# SCH_lab_1_2026-07-23.net
KiCad netlist of a schematic drawn in EasyEDA
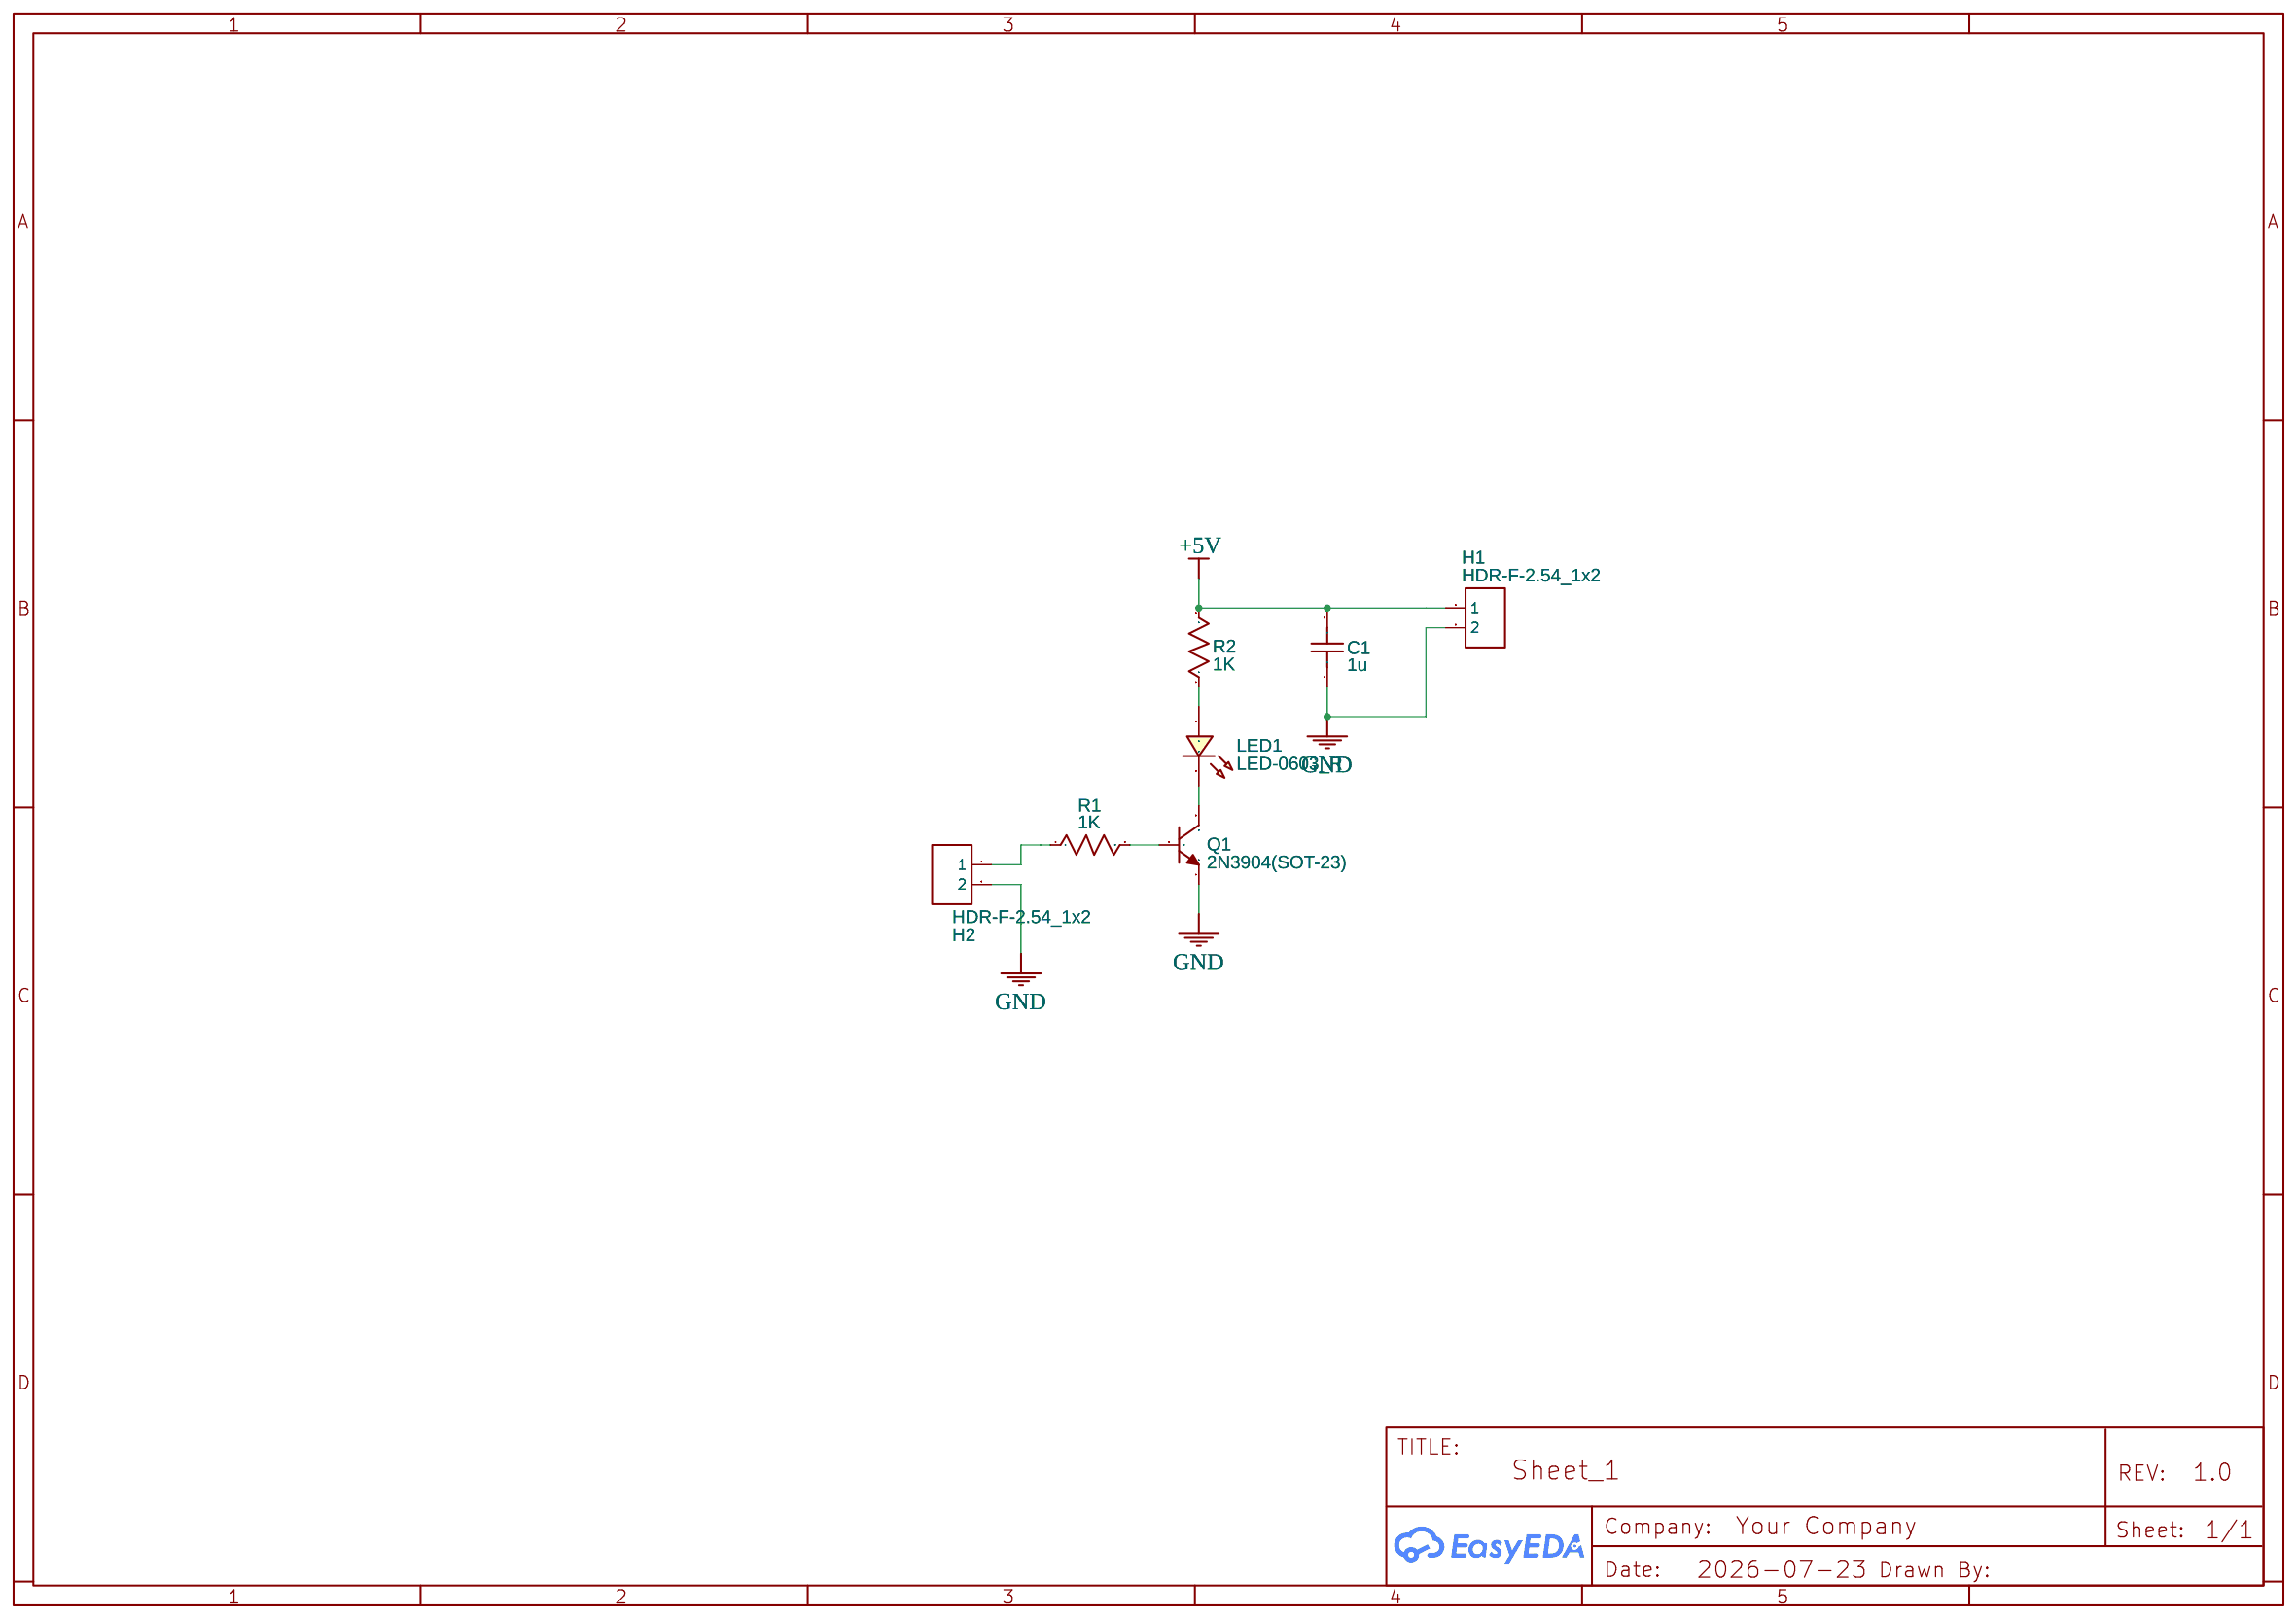
[diagram p0: schematic sheet]

(export (version "E")
  (design (tool "Eeschema 10.0.6"))
  (components
    (comp (ref "C1") (value "1u") (libsource (lib "") (part "Capacitor_US")))
    (comp (ref "H1") (value "HDR-F-2.54_1x2") (libsource (lib "") (part "HDR-F-2.54_1x2_1")))
    (comp (ref "H2") (value "HDR-F-2.54_1x2") (libsource (lib "") (part "HDR-F-2.54_1x2")))
    (comp (ref "LED1")
      (value "LED-0603_R")
      (fields
        (field (name "Manufacturer Part") "19-217/R6C-AL1M2VY/3T")
        (field (name "Manufacturer") "EVERLIGHT(台湾亿光)")
      )
      (libsource (lib "") (part "LED-0603_R"))
    )
    (comp (ref "Q1")
      (value "2N3904(SOT-23)")
      (fields (field (name "Manufacturer Part") "2n3904S-RTK/PS") (field (name "Manufacturer") "KEC"))
      (libsource (lib "") (part "2N3904(SOT-23)"))
    )
    (comp (ref "R1") (value "1K") (libsource (lib "") (part "Resistor_US_1")))
    (comp (ref "R2") (value "1K") (libsource (lib "") (part "Resistor_US")))
  )
  (nets
    (net (code "1") (name "+5V") (class "Default")
      (node (ref "C1") (pin "2") (pinfunction "2_2") (pintype "unspecified"))
      (node (ref "H1") (pin "1") (pinfunction "1_1") (pintype "input"))
      (node (ref "R2") (pin "2") (pinfunction "2_2") (pintype "unspecified"))
    )
    (net (code "2") (name "GND") (class "Default")
      (node (ref "C1") (pin "1") (pinfunction "1_1") (pintype "unspecified"))
      (node (ref "H1") (pin "2") (pinfunction "2_2") (pintype "input"))
      (node (ref "H2") (pin "2") (pinfunction "2_2") (pintype "input"))
      (node (ref "Q1") (pin "1") (pinfunction "E_1") (pintype "input"))
    )
    (net (code "3") (name "Net-(H2-Pad1)") (class "Default")
      (node (ref "H2") (pin "1") (pinfunction "1_1") (pintype "input"))
      (node (ref "R1") (pin "1") (pinfunction "1_1") (pintype "unspecified"))
    )
    (net (code "4") (name "Net-(LED1-Pad1)") (class "Default")
      (node (ref "LED1") (pin "1") (pinfunction "1_1") (pintype "unspecified"))
      (node (ref "R2") (pin "1") (pinfunction "1_1") (pintype "unspecified"))
    )
    (net (code "5") (name "Net-(Q1-B)") (class "Default")
      (node (ref "Q1") (pin "2") (pinfunction "B_2") (pintype "input"))
      (node (ref "R1") (pin "2") (pinfunction "2_2") (pintype "unspecified"))
    )
    (net (code "6") (name "Net-(Q1-C)") (class "Default")
      (node (ref "LED1") (pin "2") (pinfunction "2_2") (pintype "unspecified"))
      (node (ref "Q1") (pin "3") (pinfunction "C_3") (pintype "input"))
    )
  )
)
